# Legoduino.net
KiCad netlist of a schematic drawn in EAGLE
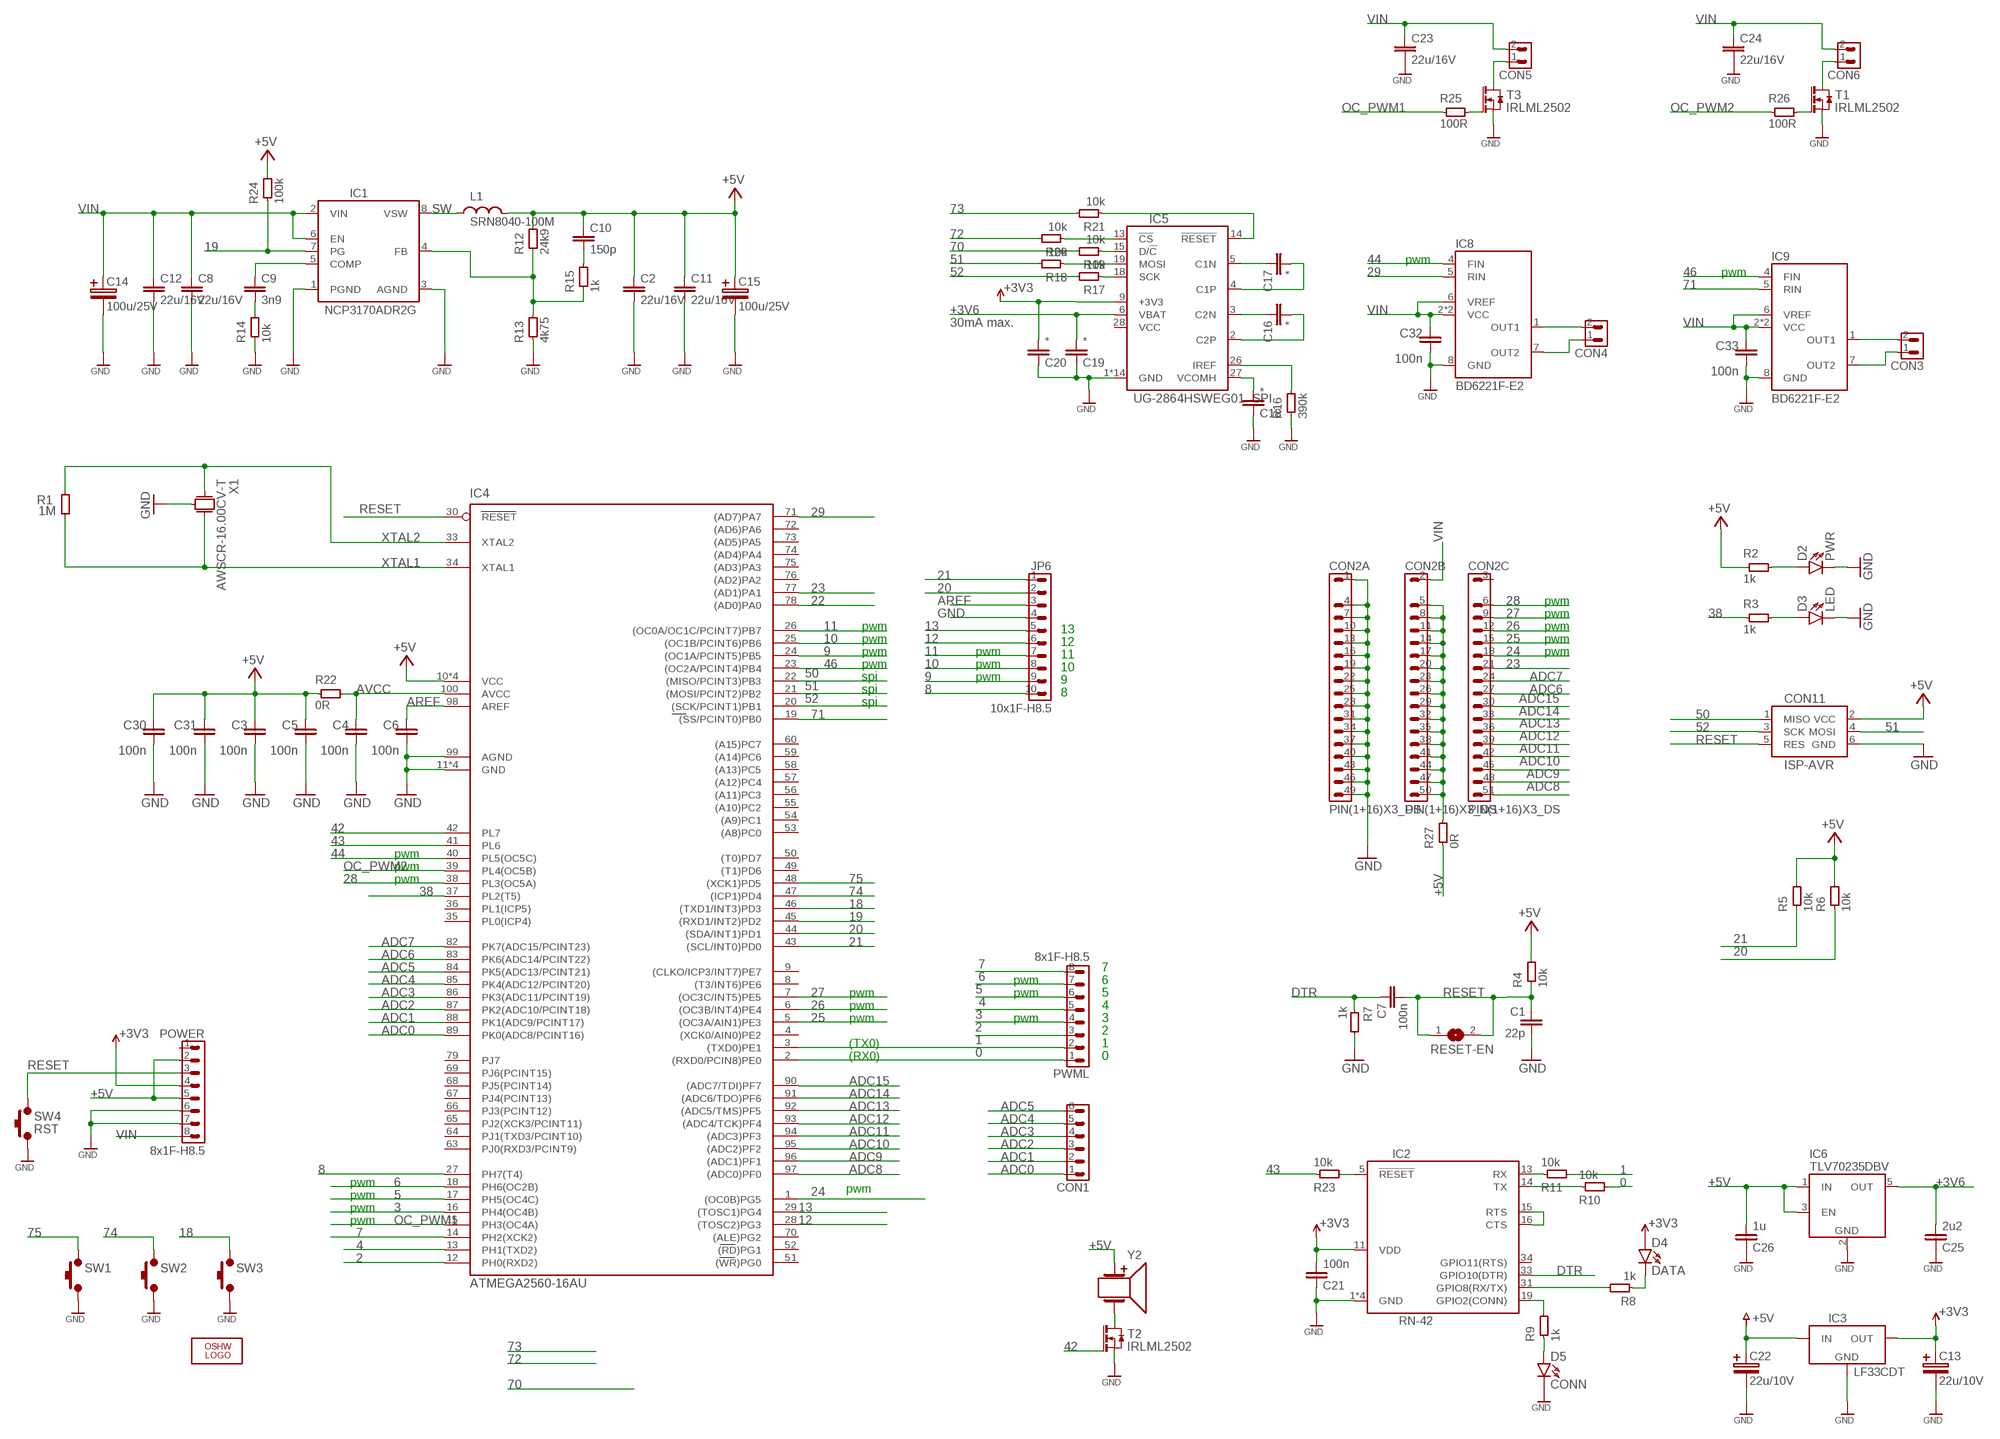
[diagram p0: schematic, sheet 1]

(export (version "E")
  (design (tool "Eeschema 10.0.6"))
  (components
    (comp (ref "C1")
      (value "22p")
      (footprint "eagle-import:0603")
      (libsource (lib "eagle-import") (part "C0603"))
    )
    (comp (ref "C2")
      (value "22u/16V")
      (footprint "eagle-import:1210")
      (libsource (lib "eagle-import") (part "C1210"))
    )
    (comp (ref "C3")
      (value "100n")
      (footprint "eagle-import:0603")
      (libsource (lib "eagle-import") (part "C0603"))
    )
    (comp (ref "C4")
      (value "100n")
      (footprint "eagle-import:0603")
      (libsource (lib "eagle-import") (part "C0603"))
    )
    (comp (ref "C5")
      (value "100n")
      (footprint "eagle-import:0603")
      (libsource (lib "eagle-import") (part "C0603"))
    )
    (comp (ref "C6")
      (value "100n")
      (footprint "eagle-import:0603")
      (libsource (lib "eagle-import") (part "C0603"))
    )
    (comp (ref "C7")
      (value "100n")
      (footprint "eagle-import:0603")
      (libsource (lib "eagle-import") (part "C0603"))
    )
    (comp (ref "C8")
      (value "22u/16V")
      (footprint "eagle-import:1210")
      (libsource (lib "eagle-import") (part "C1210"))
    )
    (comp (ref "C9")
      (value "3n9")
      (footprint "eagle-import:0603")
      (libsource (lib "eagle-import") (part "C0603"))
    )
    (comp (ref "C10")
      (value "150p")
      (footprint "eagle-import:0603")
      (libsource (lib "eagle-import") (part "C0603"))
    )
    (comp (ref "C11")
      (value "22u/16V")
      (footprint "eagle-import:1210")
      (libsource (lib "eagle-import") (part "C1210"))
    )
    (comp (ref "C12")
      (value "22u/16V")
      (footprint "eagle-import:1210")
      (libsource (lib "eagle-import") (part "C1210"))
    )
    (comp (ref "C13")
      (value "22u/10V")
      (footprint "eagle-import:SMC_A")
      (libsource (lib "eagle-import") (part "Pietrucha_CE-SMC_A"))
    )
    (comp (ref "C14")
      (value "100u/25V")
      (footprint "eagle-import:CE_SMD6.3")
      (libsource (lib "eagle-import") (part "CE_SMD6.3"))
    )
    (comp (ref "C15")
      (value "100u/25V")
      (footprint "eagle-import:CE_SMD6.3")
      (libsource (lib "eagle-import") (part "CE_SMD6.3"))
    )
    (comp (ref "C16")
      (value "*")
      (footprint "eagle-import:0603")
      (libsource (lib "eagle-import") (part "C0603"))
    )
    (comp (ref "C17")
      (value "*")
      (footprint "eagle-import:0603")
      (libsource (lib "eagle-import") (part "C0603"))
    )
    (comp (ref "C18")
      (value "*")
      (footprint "eagle-import:0603")
      (libsource (lib "eagle-import") (part "C0603"))
    )
    (comp (ref "C19")
      (value "*")
      (footprint "eagle-import:0603")
      (libsource (lib "eagle-import") (part "C0603"))
    )
    (comp (ref "C20")
      (value "*")
      (footprint "eagle-import:0603")
      (libsource (lib "eagle-import") (part "C0603"))
    )
    (comp (ref "C21")
      (value "100n")
      (footprint "eagle-import:0603")
      (libsource (lib "eagle-import") (part "C0603"))
    )
    (comp (ref "C22")
      (value "22u/10V")
      (footprint "eagle-import:SMC_A")
      (libsource (lib "eagle-import") (part "Pietrucha_CE-SMC_A"))
    )
    (comp (ref "C23")
      (value "22u/16V")
      (footprint "eagle-import:1210")
      (libsource (lib "eagle-import") (part "C1210"))
    )
    (comp (ref "C24")
      (value "22u/16V")
      (footprint "eagle-import:1210")
      (libsource (lib "eagle-import") (part "C1210"))
    )
    (comp (ref "C25")
      (value "2u2")
      (footprint "eagle-import:0603")
      (libsource (lib "eagle-import") (part "C0603"))
    )
    (comp (ref "C26")
      (value "1u")
      (footprint "eagle-import:0603")
      (libsource (lib "eagle-import") (part "C0603"))
    )
    (comp (ref "C30")
      (value "100n")
      (footprint "eagle-import:0603")
      (libsource (lib "eagle-import") (part "C0603"))
    )
    (comp (ref "C31")
      (value "100n")
      (footprint "eagle-import:0603")
      (libsource (lib "eagle-import") (part "C0603"))
    )
    (comp (ref "C32")
      (value "100n")
      (footprint "eagle-import:0603")
      (libsource (lib "eagle-import") (part "C0603"))
    )
    (comp (ref "C33")
      (value "100n")
      (footprint "eagle-import:0603")
      (libsource (lib "eagle-import") (part "C0603"))
    )
    (comp (ref "CON1")
      (value "PIN6X1C")
      (footprint "eagle-import:PIN6X1C")
      (libsource (lib "eagle-import") (part "PIN6X1C"))
    )
    (comp (ref "CON2")
      (value "PIN(1+16)X3_DS")
      (footprint "eagle-import:PIN(1+16)X3_DS")
      (libsource (lib "eagle-import") (part "PIN(1+16)X3_DS"))
    )
    (comp (ref "CON3")
      (value "PIN2X1C")
      (footprint "eagle-import:PIN2X1C")
      (libsource (lib "eagle-import") (part "PIN2X1C"))
    )
    (comp (ref "CON4")
      (value "PIN2X1C")
      (footprint "eagle-import:PIN2X1C")
      (libsource (lib "eagle-import") (part "PIN2X1C"))
    )
    (comp (ref "CON5")
      (value "PIN2X1C")
      (footprint "eagle-import:PIN2X1C")
      (libsource (lib "eagle-import") (part "PIN2X1C"))
    )
    (comp (ref "CON6")
      (value "PIN2X1C")
      (footprint "eagle-import:PIN2X1C")
      (libsource (lib "eagle-import") (part "PIN2X1C"))
    )
    (comp (ref "CON11")
      (value "ISP-AVR")
      (footprint "eagle-import:PIN3X2")
      (libsource (lib "eagle-import") (part "ISP-AVR"))
    )
    (comp (ref "D2")
      (value "PWR")
      (footprint "eagle-import:D0805")
      (libsource (lib "eagle-import") (part "LED0805"))
    )
    (comp (ref "D3")
      (value "LED")
      (footprint "eagle-import:D0805")
      (libsource (lib "eagle-import") (part "LED0805"))
    )
    (comp (ref "D4")
      (value "DATA")
      (footprint "eagle-import:D0805")
      (libsource (lib "eagle-import") (part "LED0805"))
    )
    (comp (ref "D5")
      (value "CONN")
      (footprint "eagle-import:D0805")
      (libsource (lib "eagle-import") (part "LED0805"))
    )
    (comp (ref "IC1")
      (value "NCP3170ADR2G")
      (footprint "eagle-import:SO08")
      (libsource (lib "eagle-import") (part "NCP3170DR2GA"))
    )
    (comp (ref "IC2")
      (value "RN-42")
      (footprint "eagle-import:RN42")
      (libsource (lib "eagle-import") (part "RN-42"))
    )
    (comp (ref "IC3")
      (value "LF33CDT")
      (footprint "eagle-import:DPAK")
      (libsource (lib "eagle-import") (part "LFCDT33"))
    )
    (comp (ref "IC4")
      (value "ATMEGA2560-16AU")
      (footprint "eagle-import:TQFP100")
      (libsource (lib "eagle-import") (part "ATMEGA2560AU-16"))
    )
    (comp (ref "IC5")
      (value "UG-2864HSWEG01_SPI")
      (footprint "eagle-import:UG-2864HSWEG01")
      (libsource (lib "eagle-import") (part "UG-2864HSWEG01_SPI"))
    )
    (comp (ref "IC6")
      (value "TLV70235DBV")
      (footprint "eagle-import:SOT23-5")
      (libsource (lib "eagle-import") (part "TLV702DBV35"))
    )
    (comp (ref "IC8")
      (value "BD6221F-E2")
      (footprint "eagle-import:SO08")
      (libsource (lib "eagle-import") (part "BD6221F-E2"))
    )
    (comp (ref "IC9")
      (value "BD6221F-E2")
      (footprint "eagle-import:SO08")
      (libsource (lib "eagle-import") (part "BD6221F-E2"))
    )
    (comp (ref "JP6")
      (value "10x1F-H8.5")
      (footprint "eagle-import:PIN10X1C")
      (libsource (lib "eagle-import") (part "PIN10X1C"))
    )
    (comp (ref "L1")
      (value "SRN8040-100M")
      (footprint "eagle-import:SRN8040")
      (libsource (lib "eagle-import") (part "SRN8040-100M"))
    )
    (comp (ref "LOGO1")
      (value "OSHW_LOGO_10MILX0200-NT")
      (footprint "eagle-import:OSHW_10X200_NOTEXT")
      (libsource (lib "eagle-import") (part "OSHW_LOGO_10MILX0200-NT"))
    )
    (comp (ref "POWER")
      (value "8x1F-H8.5")
      (footprint "eagle-import:PIN8X1C")
      (libsource (lib "eagle-import") (part "PIN8X1C"))
    )
    (comp (ref "PWML")
      (value "8x1F-H8.5")
      (footprint "eagle-import:PIN8X1C")
      (libsource (lib "eagle-import") (part "PIN8X1C"))
    )
    (comp (ref "R1")
      (value "1M")
      (footprint "eagle-import:0603")
      (libsource (lib "eagle-import") (part "R0603"))
    )
    (comp (ref "R2")
      (value "1k")
      (footprint "eagle-import:0603")
      (libsource (lib "eagle-import") (part "R0603"))
    )
    (comp (ref "R3")
      (value "1k")
      (footprint "eagle-import:0603")
      (libsource (lib "eagle-import") (part "R0603"))
    )
    (comp (ref "R4")
      (value "10k")
      (footprint "eagle-import:0603")
      (libsource (lib "eagle-import") (part "R0603"))
    )
    (comp (ref "R5")
      (value "10k")
      (footprint "eagle-import:0603")
      (libsource (lib "eagle-import") (part "R0603"))
    )
    (comp (ref "R6")
      (value "10k")
      (footprint "eagle-import:0603")
      (libsource (lib "eagle-import") (part "R0603"))
    )
    (comp (ref "R7")
      (value "1k")
      (footprint "eagle-import:0603")
      (libsource (lib "eagle-import") (part "R0603"))
    )
    (comp (ref "R8")
      (value "1k")
      (footprint "eagle-import:0603")
      (libsource (lib "eagle-import") (part "R0603"))
    )
    (comp (ref "R9")
      (value "1k")
      (footprint "eagle-import:0603")
      (libsource (lib "eagle-import") (part "R0603"))
    )
    (comp (ref "R10")
      (value "10k")
      (footprint "eagle-import:0603")
      (libsource (lib "eagle-import") (part "R0603"))
    )
    (comp (ref "R11")
      (value "10k")
      (footprint "eagle-import:0603")
      (libsource (lib "eagle-import") (part "R0603"))
    )
    (comp (ref "R12")
      (value "24k9")
      (footprint "eagle-import:0603")
      (libsource (lib "eagle-import") (part "R0603"))
    )
    (comp (ref "R13")
      (value "4k75")
      (footprint "eagle-import:0603")
      (libsource (lib "eagle-import") (part "R0603"))
    )
    (comp (ref "R14")
      (value "10k")
      (footprint "eagle-import:0603")
      (libsource (lib "eagle-import") (part "R0603"))
    )
    (comp (ref "R15")
      (value "1k")
      (footprint "eagle-import:0603")
      (libsource (lib "eagle-import") (part "R0603"))
    )
    (comp (ref "R16")
      (value "390k")
      (footprint "eagle-import:0603")
      (libsource (lib "eagle-import") (part "R0603"))
    )
    (comp (ref "R17")
      (value "10k")
      (footprint "eagle-import:0603")
      (libsource (lib "eagle-import") (part "R0603"))
    )
    (comp (ref "R18")
      (value "10k")
      (footprint "eagle-import:0603")
      (libsource (lib "eagle-import") (part "R0603"))
    )
    (comp (ref "R19")
      (value "10k")
      (footprint "eagle-import:0603")
      (libsource (lib "eagle-import") (part "R0603"))
    )
    (comp (ref "R20")
      (value "10k")
      (footprint "eagle-import:0603")
      (libsource (lib "eagle-import") (part "R0603"))
    )
    (comp (ref "R21")
      (value "10k")
      (footprint "eagle-import:0603")
      (libsource (lib "eagle-import") (part "R0603"))
    )
    (comp (ref "R22")
      (value "0R")
      (footprint "eagle-import:0603")
      (libsource (lib "eagle-import") (part "R0603"))
    )
    (comp (ref "R23")
      (value "10k")
      (footprint "eagle-import:0603")
      (libsource (lib "eagle-import") (part "R0603"))
    )
    (comp (ref "R24")
      (value "100k")
      (footprint "eagle-import:0603")
      (libsource (lib "eagle-import") (part "R0603"))
    )
    (comp (ref "R25")
      (value "100R")
      (footprint "eagle-import:0603")
      (libsource (lib "eagle-import") (part "R0603"))
    )
    (comp (ref "R26")
      (value "100R")
      (footprint "eagle-import:0603")
      (libsource (lib "eagle-import") (part "R0603"))
    )
    (comp (ref "R27")
      (value "0R")
      (footprint "eagle-import:0805")
      (libsource (lib "eagle-import") (part "R0805"))
    )
    (comp (ref "RESET-EN")
      (value "SJ")
      (footprint "eagle-import:SJ")
      (libsource (lib "eagle-import") (part "SJ"))
    )
    (comp (ref "SW1")
      (value "SW_SMD")
      (footprint "eagle-import:MICROSW_SMD")
      (libsource (lib "eagle-import") (part "SW_SMD"))
    )
    (comp (ref "SW2")
      (value "SW_SMD")
      (footprint "eagle-import:MICROSW_SMD")
      (libsource (lib "eagle-import") (part "SW_SMD"))
    )
    (comp (ref "SW3")
      (value "SW_SMD")
      (footprint "eagle-import:MICROSW_SMD")
      (libsource (lib "eagle-import") (part "SW_SMD"))
    )
    (comp (ref "SW4")
      (value "RST")
      (footprint "eagle-import:MICROSW_SMD")
      (libsource (lib "eagle-import") (part "SW_SMD"))
    )
    (comp (ref "T1")
      (value "IRLML2502")
      (footprint "eagle-import:SOT23")
      (libsource (lib "eagle-import") (part "IRLML2502"))
    )
    (comp (ref "T2")
      (value "IRLML2502")
      (footprint "eagle-import:SOT23")
      (libsource (lib "eagle-import") (part "IRLML2502"))
    )
    (comp (ref "T3")
      (value "IRLML2502")
      (footprint "eagle-import:SOT23")
      (libsource (lib "eagle-import") (part "IRLML2502"))
    )
    (comp (ref "X1")
      (value "AWSCR-16.00CV-T")
      (footprint "eagle-import:CERAMIC_3.7X3.1")
      (libsource (lib "eagle-import") (part "AWSCRCV-T-16.00"))
    )
    (comp (ref "Y2")
      (value "BUZZER-HCM")
      (footprint "eagle-import:BUZZER-HCM")
      (libsource (lib "eagle-import") (part "BUZZER-HCM"))
    )
  )
  (nets
    (net (code "1") (name "+3V3") (class "Default")
      (node (ref "C13") (pin "+") (pinfunction "+_+") (pintype "passive"))
      (node (ref "C20") (pin "2") (pinfunction "2_2") (pintype "passive"))
      (node (ref "C21") (pin "2") (pinfunction "2_2") (pintype "passive"))
      (node (ref "D4") (pin "A") (pinfunction "A_A") (pintype "passive"))
      (node (ref "IC2") (pin "11") (pinfunction "VDD_11") (pintype "power_in"))
      (node (ref "IC3") (pin "3") (pinfunction "OUT_3") (pintype "passive"))
      (node (ref "IC5") (pin "9") (pinfunction "+3V3_9") (pintype "power_in"))
      (node (ref "POWER") (pin "4") (pinfunction "4_4") (pintype "passive"))
    )
    (net (code "2") (name "+5V") (class "Default")
      (node (ref "C10") (pin "1") (pinfunction "1_1") (pintype "passive"))
      (node (ref "C11") (pin "1") (pinfunction "1_1") (pintype "passive"))
      (node (ref "C15") (pin "+") (pinfunction "+_+") (pintype "passive"))
      (node (ref "C2") (pin "1") (pinfunction "1_1") (pintype "passive"))
      (node (ref "C22") (pin "+") (pinfunction "+_+") (pintype "passive"))
      (node (ref "C26") (pin "2") (pinfunction "2_2") (pintype "passive"))
      (node (ref "C3") (pin "1") (pinfunction "1_1") (pintype "passive"))
      (node (ref "C30") (pin "1") (pinfunction "1_1") (pintype "passive"))
      (node (ref "C31") (pin "1") (pinfunction "1_1") (pintype "passive"))
      (node (ref "C5") (pin "1") (pinfunction "1_1") (pintype "passive"))
      (node (ref "CON11") (pin "2") (pinfunction "VCC_2") (pintype "passive"))
      (node (ref "IC3") (pin "1") (pinfunction "IN_1") (pintype "input"))
      (node (ref "IC4") (pin "10") (pinfunction "VCC_10") (pintype "power_in"))
      (node (ref "IC4") (pin "31") (pinfunction "VCC_31") (pintype "power_in"))
      (node (ref "IC4") (pin "61") (pinfunction "VCC_61") (pintype "power_in"))
      (node (ref "IC4") (pin "80") (pinfunction "VCC_80") (pintype "power_in"))
      (node (ref "IC6") (pin "1") (pinfunction "IN_1") (pintype "input"))
      (node (ref "IC6") (pin "3") (pinfunction "EN_3") (pintype "input"))
      (node (ref "L1") (pin "2") (pinfunction "2_2") (pintype "passive"))
      (node (ref "POWER") (pin "2") (pinfunction "2_2") (pintype "passive"))
      (node (ref "POWER") (pin "5") (pinfunction "5_5") (pintype "passive"))
      (node (ref "R12") (pin "2") (pinfunction "2_2") (pintype "passive"))
      (node (ref "R2") (pin "1") (pinfunction "1_1") (pintype "passive"))
      (node (ref "R22") (pin "1") (pinfunction "1_1") (pintype "passive"))
      (node (ref "R24") (pin "2") (pinfunction "2_2") (pintype "passive"))
      (node (ref "R27") (pin "1") (pinfunction "1_1") (pintype "passive"))
      (node (ref "R4") (pin "2") (pinfunction "2_2") (pintype "passive"))
      (node (ref "R5") (pin "2") (pinfunction "2_2") (pintype "passive"))
      (node (ref "R6") (pin "2") (pinfunction "2_2") (pintype "passive"))
      (node (ref "Y2") (pin "+") (pinfunction "+_+") (pintype "passive"))
    )
    (net (code "3") (name "/+3V6") (class "Default")
      (node (ref "C19") (pin "2") (pinfunction "2_2") (pintype "passive"))
      (node (ref "C25") (pin "2") (pinfunction "2_2") (pintype "passive"))
      (node (ref "IC5") (pin "6") (pinfunction "VBAT_6") (pintype "power_in"))
      (node (ref "IC6") (pin "5") (pinfunction "OUT_5") (pintype "passive"))
    )
    (net (code "4") (name "/0") (class "Default")
      (node (ref "IC4") (pin "2") (pinfunction "(RXD0/PCIN8)PE0_2") (pintype "bidirectional"))
      (node (ref "PWML") (pin "1") (pinfunction "1_1") (pintype "passive"))
      (node (ref "R10") (pin "2") (pinfunction "2_2") (pintype "passive"))
    )
    (net (code "5") (name "/1") (class "Default")
      (node (ref "IC4") (pin "3") (pinfunction "(TXD0)PE1_3") (pintype "bidirectional"))
      (node (ref "PWML") (pin "2") (pinfunction "2_2") (pintype "passive"))
      (node (ref "R11") (pin "2") (pinfunction "2_2") (pintype "passive"))
    )
    (net (code "6") (name "/2") (class "Default")
      (node (ref "IC4") (pin "12") (pinfunction "PH0(RXD2)_12") (pintype "bidirectional"))
      (node (ref "PWML") (pin "3") (pinfunction "3_3") (pintype "passive"))
    )
    (net (code "7") (name "/3") (class "Default")
      (node (ref "IC4") (pin "16") (pinfunction "PH4(OC4B)_16") (pintype "bidirectional"))
      (node (ref "PWML") (pin "4") (pinfunction "4_4") (pintype "passive"))
    )
    (net (code "8") (name "/4") (class "Default")
      (node (ref "IC4") (pin "13") (pinfunction "PH1(TXD2)_13") (pintype "bidirectional"))
      (node (ref "PWML") (pin "5") (pinfunction "5_5") (pintype "passive"))
    )
    (net (code "9") (name "/5") (class "Default")
      (node (ref "IC4") (pin "17") (pinfunction "PH5(OC4C)_17") (pintype "bidirectional"))
      (node (ref "PWML") (pin "6") (pinfunction "6_6") (pintype "passive"))
    )
    (net (code "10") (name "/6") (class "Default")
      (node (ref "IC4") (pin "18") (pinfunction "PH6(OC2B)_18") (pintype "bidirectional"))
      (node (ref "PWML") (pin "7") (pinfunction "7_7") (pintype "passive"))
    )
    (net (code "11") (name "/7") (class "Default")
      (node (ref "IC4") (pin "14") (pinfunction "PH2(XCK2)_14") (pintype "bidirectional"))
      (node (ref "PWML") (pin "8") (pinfunction "8_8") (pintype "passive"))
    )
    (net (code "12") (name "/8") (class "Default")
      (node (ref "IC4") (pin "27") (pinfunction "PH7(T4)_27") (pintype "bidirectional"))
      (node (ref "JP6") (pin "10") (pinfunction "10_10") (pintype "passive"))
    )
    (net (code "13") (name "/9") (class "Default")
      (node (ref "IC4") (pin "24") (pinfunction "(OC1A/PCINT5)PB5_24") (pintype "bidirectional"))
      (node (ref "JP6") (pin "9") (pinfunction "9_9") (pintype "passive"))
    )
    (net (code "14") (name "/10") (class "Default")
      (node (ref "IC4") (pin "25") (pinfunction "(OC1B/PCINT6)PB6_25") (pintype "bidirectional"))
      (node (ref "JP6") (pin "8") (pinfunction "8_8") (pintype "passive"))
    )
    (net (code "15") (name "/11") (class "Default")
      (node (ref "IC4") (pin "26") (pinfunction "(OC0A/OC1C/PCINT7)PB7_26") (pintype "bidirectional"))
      (node (ref "JP6") (pin "7") (pinfunction "7_7") (pintype "passive"))
    )
    (net (code "16") (name "/12") (class "Default")
      (node (ref "IC4") (pin "28") (pinfunction "(TOSC2)PG3_28") (pintype "bidirectional"))
      (node (ref "JP6") (pin "6") (pinfunction "6_6") (pintype "passive"))
    )
    (net (code "17") (name "/13") (class "Default")
      (node (ref "IC4") (pin "29") (pinfunction "(TOSC1)PG4_29") (pintype "bidirectional"))
      (node (ref "JP6") (pin "5") (pinfunction "5_5") (pintype "passive"))
    )
    (net (code "18") (name "/18") (class "Default")
      (node (ref "IC4") (pin "46") (pinfunction "(TXD1/INT3)PD3_46") (pintype "bidirectional"))
      (node (ref "SW3") (pin "1") (pinfunction "1_1") (pintype "passive"))
      (node (ref "SW3") (pin "1A") (pinfunction "1_1A") (pintype "passive"))
    )
    (net (code "19") (name "/19") (class "Default")
      (node (ref "IC1") (pin "7") (pinfunction "PG_7") (pintype "open_collector"))
      (node (ref "IC4") (pin "45") (pinfunction "(RXD1/INT2)PD2_45") (pintype "bidirectional"))
      (node (ref "R24") (pin "1") (pinfunction "1_1") (pintype "passive"))
    )
    (net (code "20") (name "/20") (class "Default")
      (node (ref "IC4") (pin "44") (pinfunction "(SDA/INT1)PD1_44") (pintype "bidirectional"))
      (node (ref "JP6") (pin "2") (pinfunction "2_2") (pintype "passive"))
      (node (ref "R6") (pin "1") (pinfunction "1_1") (pintype "passive"))
    )
    (net (code "21") (name "/21") (class "Default")
      (node (ref "IC4") (pin "43") (pinfunction "(SCL/INT0)PD0_43") (pintype "bidirectional"))
      (node (ref "JP6") (pin "1") (pinfunction "1_1") (pintype "passive"))
      (node (ref "R5") (pin "1") (pinfunction "1_1") (pintype "passive"))
    )
    (net (code "22") (name "/22") (class "Default")
      (node (ref "IC4") (pin "78") (pinfunction "(AD0)PA0_78") (pintype "bidirectional"))
    )
    (net (code "23") (name "/23") (class "Default")
      (node (ref "CON2") (pin "21") (pinfunction "7_21") (pintype "passive"))
      (node (ref "IC4") (pin "77") (pinfunction "(AD1)PA1_77") (pintype "bidirectional"))
    )
    (net (code "24") (name "/24") (class "Default")
      (node (ref "CON2") (pin "18") (pinfunction "6_18") (pintype "passive"))
      (node (ref "IC4") (pin "1") (pinfunction "(OC0B)PG5_1") (pintype "bidirectional"))
    )
    (net (code "25") (name "/25") (class "Default")
      (node (ref "CON2") (pin "15") (pinfunction "5_15") (pintype "passive"))
      (node (ref "IC4") (pin "5") (pinfunction "(OC3A/AIN1)PE3_5") (pintype "bidirectional"))
    )
    (net (code "26") (name "/26") (class "Default")
      (node (ref "CON2") (pin "12") (pinfunction "4_12") (pintype "passive"))
      (node (ref "IC4") (pin "6") (pinfunction "(OC3B/INT4)PE4_6") (pintype "bidirectional"))
    )
    (net (code "27") (name "/27") (class "Default")
      (node (ref "CON2") (pin "9") (pinfunction "3_9") (pintype "passive"))
      (node (ref "IC4") (pin "7") (pinfunction "(OC3C/INT5)PE5_7") (pintype "bidirectional"))
    )
    (net (code "28") (name "/28") (class "Default")
      (node (ref "CON2") (pin "6") (pinfunction "2_6") (pintype "passive"))
      (node (ref "IC4") (pin "38") (pinfunction "PL3(OC5A)_38") (pintype "bidirectional"))
    )
    (net (code "29") (name "/29") (class "Default")
      (node (ref "IC4") (pin "71") (pinfunction "(AD7)PA7_71") (pintype "bidirectional"))
      (node (ref "IC8") (pin "5") (pinfunction "RIN_5") (pintype "input"))
    )
    (net (code "30") (name "/38") (class "Default")
      (node (ref "IC4") (pin "37") (pinfunction "PL2(T5)_37") (pintype "bidirectional"))
      (node (ref "R3") (pin "1") (pinfunction "1_1") (pintype "passive"))
    )
    (net (code "31") (name "/42") (class "Default")
      (node (ref "IC4") (pin "42") (pinfunction "PL7_42") (pintype "bidirectional"))
      (node (ref "T2") (pin "1") (pinfunction "G_1") (pintype "passive"))
    )
    (net (code "32") (name "/43") (class "Default")
      (node (ref "IC4") (pin "41") (pinfunction "PL6_41") (pintype "bidirectional"))
      (node (ref "R23") (pin "1") (pinfunction "1_1") (pintype "passive"))
    )
    (net (code "33") (name "/44") (class "Default")
      (node (ref "IC4") (pin "40") (pinfunction "PL5(OC5C)_40") (pintype "bidirectional"))
      (node (ref "IC8") (pin "4") (pinfunction "FIN_4") (pintype "input"))
    )
    (net (code "34") (name "/46") (class "Default")
      (node (ref "IC4") (pin "23") (pinfunction "(OC2A/PCINT4)PB4_23") (pintype "bidirectional"))
      (node (ref "IC9") (pin "4") (pinfunction "FIN_4") (pintype "input"))
    )
    (net (code "35") (name "/50") (class "Default")
      (node (ref "CON11") (pin "1") (pinfunction "MISO_1") (pintype "passive"))
      (node (ref "IC4") (pin "22") (pinfunction "(MISO/PCINT3)PB3_22") (pintype "bidirectional"))
    )
    (net (code "36") (name "/51") (class "Default")
      (node (ref "CON11") (pin "4") (pinfunction "MOSI_4") (pintype "passive"))
      (node (ref "IC4") (pin "21") (pinfunction "(MOSI/PCINT2)PB2_21") (pintype "bidirectional"))
      (node (ref "R18") (pin "2") (pinfunction "2_2") (pintype "passive"))
    )
    (net (code "37") (name "/52") (class "Default")
      (node (ref "CON11") (pin "3") (pinfunction "SCK_3") (pintype "passive"))
      (node (ref "IC4") (pin "20") (pinfunction "(SCK/PCINT1)PB1_20") (pintype "bidirectional"))
      (node (ref "R17") (pin "2") (pinfunction "2_2") (pintype "passive"))
    )
    (net (code "38") (name "/70") (class "Default")
      (node (ref "R19") (pin "2") (pinfunction "2_2") (pintype "passive"))
    )
    (net (code "39") (name "/71") (class "Default")
      (node (ref "IC4") (pin "19") (pinfunction "(SS/PCINT0)PB0_19") (pintype "bidirectional"))
      (node (ref "IC9") (pin "5") (pinfunction "RIN_5") (pintype "input"))
    )
    (net (code "40") (name "/72") (class "Default")
      (node (ref "R20") (pin "2") (pinfunction "2_2") (pintype "passive"))
    )
    (net (code "41") (name "/73") (class "Default")
      (node (ref "R21") (pin "2") (pinfunction "2_2") (pintype "passive"))
    )
    (net (code "42") (name "/74") (class "Default")
      (node (ref "IC4") (pin "47") (pinfunction "(ICP1)PD4_47") (pintype "bidirectional"))
      (node (ref "SW2") (pin "1") (pinfunction "1_1") (pintype "passive"))
      (node (ref "SW2") (pin "1A") (pinfunction "1_1A") (pintype "passive"))
    )
    (net (code "43") (name "/75") (class "Default")
      (node (ref "IC4") (pin "48") (pinfunction "(XCK1)PD5_48") (pintype "bidirectional"))
      (node (ref "SW1") (pin "1") (pinfunction "1_1") (pintype "passive"))
      (node (ref "SW1") (pin "1A") (pinfunction "1_1A") (pintype "passive"))
    )
    (net (code "44") (name "/ADC0") (class "Default")
      (node (ref "CON1") (pin "1") (pinfunction "1_1") (pintype "passive"))
      (node (ref "IC4") (pin "89") (pinfunction "PK0(ADC8/PCINT16)_89") (pintype "bidirectional"))
    )
    (net (code "45") (name "/ADC1") (class "Default")
      (node (ref "CON1") (pin "2") (pinfunction "2_2") (pintype "passive"))
      (node (ref "IC4") (pin "88") (pinfunction "PK1(ADC9/PCINT17)_88") (pintype "bidirectional"))
    )
    (net (code "46") (name "/ADC2") (class "Default")
      (node (ref "CON1") (pin "3") (pinfunction "3_3") (pintype "passive"))
      (node (ref "IC4") (pin "87") (pinfunction "PK2(ADC10/PCINT18)_87") (pintype "bidirectional"))
    )
    (net (code "47") (name "/ADC3") (class "Default")
      (node (ref "CON1") (pin "4") (pinfunction "4_4") (pintype "passive"))
      (node (ref "IC4") (pin "86") (pinfunction "PK3(ADC11/PCINT19)_86") (pintype "bidirectional"))
    )
    (net (code "48") (name "/ADC4") (class "Default")
      (node (ref "CON1") (pin "5") (pinfunction "5_5") (pintype "passive"))
      (node (ref "IC4") (pin "85") (pinfunction "PK4(ADC12/PCINT20)_85") (pintype "bidirectional"))
    )
    (net (code "49") (name "/ADC5") (class "Default")
      (node (ref "CON1") (pin "6") (pinfunction "6_6") (pintype "passive"))
      (node (ref "IC4") (pin "84") (pinfunction "PK5(ADC13/PCINT21)_84") (pintype "bidirectional"))
    )
    (net (code "50") (name "/ADC6") (class "Default")
      (node (ref "CON2") (pin "27") (pinfunction "9_27") (pintype "passive"))
      (node (ref "IC4") (pin "83") (pinfunction "PK6(ADC14/PCINT22)_83") (pintype "bidirectional"))
    )
    (net (code "51") (name "/ADC7") (class "Default")
      (node (ref "CON2") (pin "24") (pinfunction "8_24") (pintype "passive"))
      (node (ref "IC4") (pin "82") (pinfunction "PK7(ADC15/PCINT23)_82") (pintype "bidirectional"))
    )
    (net (code "52") (name "/ADC8") (class "Default")
      (node (ref "CON2") (pin "51") (pinfunction "17_51") (pintype "passive"))
      (node (ref "IC4") (pin "97") (pinfunction "(ADC0)PF0_97") (pintype "bidirectional"))
    )
    (net (code "53") (name "/ADC9") (class "Default")
      (node (ref "CON2") (pin "48") (pinfunction "16_48") (pintype "passive"))
      (node (ref "IC4") (pin "96") (pinfunction "(ADC1)PF1_96") (pintype "bidirectional"))
    )
    (net (code "54") (name "/ADC10") (class "Default")
      (node (ref "CON2") (pin "45") (pinfunction "15_45") (pintype "passive"))
      (node (ref "IC4") (pin "95") (pinfunction "(ADC2)PF2_95") (pintype "bidirectional"))
    )
    (net (code "55") (name "/ADC11") (class "Default")
      (node (ref "CON2") (pin "42") (pinfunction "14_42") (pintype "passive"))
      (node (ref "IC4") (pin "94") (pinfunction "(ADC3)PF3_94") (pintype "bidirectional"))
    )
    (net (code "56") (name "/ADC12") (class "Default")
      (node (ref "CON2") (pin "39") (pinfunction "13_39") (pintype "passive"))
      (node (ref "IC4") (pin "93") (pinfunction "(ADC4/TCK)PF4_93") (pintype "bidirectional"))
    )
    (net (code "57") (name "/ADC13") (class "Default")
      (node (ref "CON2") (pin "36") (pinfunction "12_36") (pintype "passive"))
      (node (ref "IC4") (pin "92") (pinfunction "(ADC5/TMS)PF5_92") (pintype "bidirectional"))
    )
    (net (code "58") (name "/ADC14") (class "Default")
      (node (ref "CON2") (pin "33") (pinfunction "11_33") (pintype "passive"))
      (node (ref "IC4") (pin "91") (pinfunction "(ADC6/TDO)PF6_91") (pintype "bidirectional"))
    )
    (net (code "59") (name "/ADC15") (class "Default")
      (node (ref "CON2") (pin "30") (pinfunction "10_30") (pintype "passive"))
      (node (ref "IC4") (pin "90") (pinfunction "(ADC7/TDI)PF7_90") (pintype "bidirectional"))
    )
    (net (code "60") (name "/AREF") (class "Default")
      (node (ref "C6") (pin "1") (pinfunction "1_1") (pintype "passive"))
      (node (ref "IC4") (pin "98") (pinfunction "AREF_98") (pintype "bidirectional"))
      (node (ref "JP6") (pin "3") (pinfunction "3_3") (pintype "passive"))
    )
    (net (code "61") (name "/AVCC") (class "Default")
      (node (ref "C4") (pin "1") (pinfunction "1_1") (pintype "passive"))
      (node (ref "IC4") (pin "100") (pinfunction "AVCC_100") (pintype "power_in"))
      (node (ref "R22") (pin "2") (pinfunction "2_2") (pintype "passive"))
    )
    (net (code "62") (name "/DTR") (class "Default")
      (node (ref "C7") (pin "1") (pinfunction "1_1") (pintype "passive"))
      (node (ref "IC2") (pin "33") (pinfunction "GPIO10(DTR)_33") (pintype "bidirectional"))
      (node (ref "R7") (pin "1") (pinfunction "1_1") (pintype "passive"))
    )
    (net (code "63") (name "/OC_PWM1") (class "Default")
      (node (ref "IC4") (pin "15") (pinfunction "PH3(OC4A)_15") (pintype "bidirectional"))
      (node (ref "R25") (pin "1") (pinfunction "1_1") (pintype "passive"))
    )
    (net (code "64") (name "/OC_PWM2") (class "Default")
      (node (ref "IC4") (pin "39") (pinfunction "PL4(OC5B)_39") (pintype "bidirectional"))
      (node (ref "R26") (pin "1") (pinfunction "1_1") (pintype "passive"))
    )
    (net (code "65") (name "/RESET") (class "Default")
      (node (ref "C1") (pin "1") (pinfunction "1_1") (pintype "passive"))
      (node (ref "C7") (pin "2") (pinfunction "2_2") (pintype "passive"))
      (node (ref "CON11") (pin "5") (pinfunction "RES_5") (pintype "passive"))
      (node (ref "IC4") (pin "30") (pinfunction "RESET_30") (pintype "input"))
      (node (ref "POWER") (pin "3") (pinfunction "3_3") (pintype "passive"))
      (node (ref "R4") (pin "1") (pinfunction "1_1") (pintype "passive"))
      (node (ref "RESET-EN") (pin "1") (pinfunction "1_1") (pintype "passive"))
      (node (ref "RESET-EN") (pin "2") (pinfunction "2_2") (pintype "passive"))
      (node (ref "SW4") (pin "1") (pinfunction "1_1") (pintype "passive"))
      (node (ref "SW4") (pin "1A") (pinfunction "1_1A") (pintype "passive"))
    )
    (net (code "66") (name "/SW") (class "Default")
      (node (ref "IC1") (pin "8") (pinfunction "VSW_8") (pintype "output"))
      (node (ref "L1") (pin "1") (pinfunction "1_1") (pintype "passive"))
    )
    (net (code "67") (name "/VCC") (class "Default")
      (node (ref "IC5") (pin "28") (pinfunction "VCC_28") (pintype "power_in"))
    )
    (net (code "68") (name "/VIN") (class "Default")
      (node (ref "C12") (pin "1") (pinfunction "1_1") (pintype "passive"))
      (node (ref "C14") (pin "+") (pinfunction "+_+") (pintype "passive"))
      (node (ref "C23") (pin "1") (pinfunction "1_1") (pintype "passive"))
      (node (ref "C24") (pin "1") (pinfunction "1_1") (pintype "passive"))
      (node (ref "C32") (pin "1") (pinfunction "1_1") (pintype "passive"))
      (node (ref "C33") (pin "1") (pinfunction "1_1") (pintype "passive"))
      (node (ref "C8") (pin "1") (pinfunction "1_1") (pintype "passive"))
      (node (ref "CON2") (pin "2") (pinfunction "1_2") (pintype "passive"))
      (node (ref "CON5") (pin "2") (pinfunction "2_2") (pintype "passive"))
      (node (ref "CON6") (pin "2") (pinfunction "2_2") (pintype "passive"))
      (node (ref "IC1") (pin "2") (pinfunction "VIN_2") (pintype "power_in"))
      (node (ref "IC1") (pin "6") (pinfunction "EN_6") (pintype "input"))
      (node (ref "IC8") (pin "2") (pinfunction "VCC_2") (pintype "power_in"))
      (node (ref "IC8") (pin "3") (pinfunction "VCC_3") (pintype "power_in"))
      (node (ref "IC8") (pin "6") (pinfunction "VREF_6") (pintype "input"))
      (node (ref "IC9") (pin "2") (pinfunction "VCC_2") (pintype "power_in"))
      (node (ref "IC9") (pin "3") (pinfunction "VCC_3") (pintype "power_in"))
      (node (ref "IC9") (pin "6") (pinfunction "VREF_6") (pintype "input"))
      (node (ref "POWER") (pin "8") (pinfunction "8_8") (pintype "passive"))
    )
    (net (code "69") (name "/XTAL1") (class "Default")
      (node (ref "IC4") (pin "34") (pinfunction "XTAL1_34") (pintype "input"))
      (node (ref "R1") (pin "1") (pinfunction "1_1") (pintype "passive"))
      (node (ref "X1") (pin "2") (pinfunction "2_2") (pintype "passive"))
    )
    (net (code "70") (name "/XTAL2") (class "Default")
      (node (ref "IC4") (pin "33") (pinfunction "XTAL2_33") (pintype "output"))
      (node (ref "R1") (pin "2") (pinfunction "2_2") (pintype "passive"))
      (node (ref "X1") (pin "1") (pinfunction "1_1") (pintype "passive"))
    )
    (net (code "71") (name "GND") (class "Default")
      (node (ref "C1") (pin "2") (pinfunction "2_2") (pintype "passive"))
      (node (ref "C11") (pin "2") (pinfunction "2_2") (pintype "passive"))
      (node (ref "C12") (pin "2") (pinfunction "2_2") (pintype "passive"))
      (node (ref "C13") (pin "-") (pinfunction "-_-") (pintype "passive"))
      (node (ref "C14") (pin "-") (pinfunction "-_-") (pintype "passive"))
      (node (ref "C15") (pin "-") (pinfunction "-_-") (pintype "passive"))
      (node (ref "C18") (pin "1") (pinfunction "1_1") (pintype "passive"))
      (node (ref "C19") (pin "1") (pinfunction "1_1") (pintype "passive"))
      (node (ref "C2") (pin "2") (pinfunction "2_2") (pintype "passive"))
      (node (ref "C20") (pin "1") (pinfunction "1_1") (pintype "passive"))
      (node (ref "C21") (pin "1") (pinfunction "1_1") (pintype "passive"))
      (node (ref "C22") (pin "-") (pinfunction "-_-") (pintype "passive"))
      (node (ref "C23") (pin "2") (pinfunction "2_2") (pintype "passive"))
      (node (ref "C24") (pin "2") (pinfunction "2_2") (pintype "passive"))
      (node (ref "C25") (pin "1") (pinfunction "1_1") (pintype "passive"))
      (node (ref "C26") (pin "1") (pinfunction "1_1") (pintype "passive"))
      (node (ref "C3") (pin "2") (pinfunction "2_2") (pintype "passive"))
      (node (ref "C30") (pin "2") (pinfunction "2_2") (pintype "passive"))
      (node (ref "C31") (pin "2") (pinfunction "2_2") (pintype "passive"))
      (node (ref "C32") (pin "2") (pinfunction "2_2") (pintype "passive"))
      (node (ref "C33") (pin "2") (pinfunction "2_2") (pintype "passive"))
      (node (ref "C4") (pin "2") (pinfunction "2_2") (pintype "passive"))
      (node (ref "C5") (pin "2") (pinfunction "2_2") (pintype "passive"))
      (node (ref "C6") (pin "2") (pinfunction "2_2") (pintype "passive"))
      (node (ref "C8") (pin "2") (pinfunction "2_2") (pintype "passive"))
      (node (ref "CON11") (pin "6") (pinfunction "GND_6") (pintype "passive"))
      (node (ref "CON2") (pin "1") (pinfunction "1_1") (pintype "passive"))
      (node (ref "CON2") (pin "10") (pinfunction "4_10") (pintype "passive"))
      (node (ref "CON2") (pin "13") (pinfunction "5_13") (pintype "passive"))
      (node (ref "CON2") (pin "16") (pinfunction "6_16") (pintype "passive"))
      (node (ref "CON2") (pin "19") (pinfunction "7_19") (pintype "passive"))
      (node (ref "CON2") (pin "22") (pinfunction "8_22") (pintype "passive"))
      (node (ref "CON2") (pin "25") (pinfunction "9_25") (pintype "passive"))
      (node (ref "CON2") (pin "28") (pinfunction "10_28") (pintype "passive"))
      (node (ref "CON2") (pin "31") (pinfunction "11_31") (pintype "passive"))
      (node (ref "CON2") (pin "34") (pinfunction "12_34") (pintype "passive"))
      (node (ref "CON2") (pin "37") (pinfunction "13_37") (pintype "passive"))
      (node (ref "CON2") (pin "4") (pinfunction "2_4") (pintype "passive"))
      (node (ref "CON2") (pin "40") (pinfunction "14_40") (pintype "passive"))
      (node (ref "CON2") (pin "43") (pinfunction "15_43") (pintype "passive"))
      (node (ref "CON2") (pin "46") (pinfunction "16_46") (pintype "passive"))
      (node (ref "CON2") (pin "49") (pinfunction "17_49") (pintype "passive"))
      (node (ref "CON2") (pin "7") (pinfunction "3_7") (pintype "passive"))
      (node (ref "D2") (pin "K") (pinfunction "K_K") (pintype "passive"))
      (node (ref "D3") (pin "K") (pinfunction "K_K") (pintype "passive"))
      (node (ref "D5") (pin "K") (pinfunction "K_K") (pintype "passive"))
      (node (ref "IC1") (pin "1") (pinfunction "PGND_1") (pintype "power_in"))
      (node (ref "IC1") (pin "3") (pinfunction "AGND_3") (pintype "power_in"))
      (node (ref "IC2") (pin "1") (pinfunction "GND_1") (pintype "power_in"))
      (node (ref "IC2") (pin "12") (pinfunction "GND_12") (pintype "power_in"))
      (node (ref "IC2") (pin "28") (pinfunction "GND_28") (pintype "power_in"))
      (node (ref "IC2") (pin "29") (pinfunction "GND_29") (pintype "power_in"))
      (node (ref "IC3") (pin "2") (pinfunction "GND_2") (pintype "passive"))
      (node (ref "IC4") (pin "11") (pinfunction "GND_11") (pintype "power_in"))
      (node (ref "IC4") (pin "32") (pinfunction "GND_32") (pintype "power_in"))
      (node (ref "IC4") (pin "62") (pinfunction "GND_62") (pintype "power_in"))
      (node (ref "IC4") (pin "81") (pinfunction "GND_81") (pintype "power_in"))
      (node (ref "IC4") (pin "99") (pinfunction "AGND_99") (pintype "power_in"))
      (node (ref "IC5") (pin "1") (pinfunction "GND_1") (pintype "power_in"))
      (node (ref "IC5") (pin "10") (pinfunction "GND_10") (pintype "power_in"))
      (node (ref "IC5") (pin "11") (pinfunction "GND_11") (pintype "power_in"))
      (node (ref "IC5") (pin "12") (pinfunction "GND_12") (pintype "power_in"))
      (node (ref "IC5") (pin "16") (pinfunction "GND_16") (pintype "power_in"))
      (node (ref "IC5") (pin "17") (pinfunction "GND_17") (pintype "power_in"))
      (node (ref "IC5") (pin "21") (pinfunction "GND_21") (pintype "power_in"))
      (node (ref "IC5") (pin "22") (pinfunction "GND_22") (pintype "power_in"))
      (node (ref "IC5") (pin "23") (pinfunction "GND_23") (pintype "power_in"))
      (node (ref "IC5") (pin "24") (pinfunction "GND_24") (pintype "power_in"))
      (node (ref "IC5") (pin "25") (pinfunction "GND_25") (pintype "power_in"))
      (node (ref "IC5") (pin "29") (pinfunction "GND_29") (pintype "power_in"))
      (node (ref "IC5") (pin "30") (pinfunction "GND_30") (pintype "power_in"))
      (node (ref "IC5") (pin "8") (pinfunction "GND_8") (pintype "power_in"))
      (node (ref "IC6") (pin "2") (pinfunction "GND_2") (pintype "passive"))
      (node (ref "IC8") (pin "8") (pinfunction "GND_8") (pintype "power_in"))
      (node (ref "IC9") (pin "8") (pinfunction "GND_8") (pintype "power_in"))
      (node (ref "JP6") (pin "4") (pinfunction "4_4") (pintype "passive"))
      (node (ref "POWER") (pin "6") (pinfunction "6_6") (pintype "passive"))
      (node (ref "POWER") (pin "7") (pinfunction "7_7") (pintype "passive"))
      (node (ref "R13") (pin "1") (pinfunction "1_1") (pintype "passive"))
      (node (ref "R14") (pin "1") (pinfunction "1_1") (pintype "passive"))
      (node (ref "R16") (pin "1") (pinfunction "1_1") (pintype "passive"))
      (node (ref "R7") (pin "2") (pinfunction "2_2") (pintype "passive"))
      (node (ref "SW1") (pin "2") (pinfunction "2_2") (pintype "passive"))
      (node (ref "SW1") (pin "2A") (pinfunction "2_2A") (pintype "passive"))
      (node (ref "SW2") (pin "2") (pinfunction "2_2") (pintype "passive"))
      (node (ref "SW2") (pin "2A") (pinfunction "2_2A") (pintype "passive"))
      (node (ref "SW3") (pin "2") (pinfunction "2_2") (pintype "passive"))
      (node (ref "SW3") (pin "2A") (pinfunction "2_2A") (pintype "passive"))
      (node (ref "SW4") (pin "2") (pinfunction "2_2") (pintype "passive"))
      (node (ref "SW4") (pin "2A") (pinfunction "2_2A") (pintype "passive"))
      (node (ref "T1") (pin "2") (pinfunction "S_2") (pintype "passive"))
      (node (ref "T2") (pin "2") (pinfunction "S_2") (pintype "passive"))
      (node (ref "T3") (pin "2") (pinfunction "S_2") (pintype "passive"))
      (node (ref "X1") (pin "0") (pinfunction "0_0") (pintype "passive"))
    )
    (net (code "72") (name "Net-(C9-Pad2)") (class "Default")
      (node (ref "C9") (pin "2") (pinfunction "2_2") (pintype "passive"))
      (node (ref "R14") (pin "2") (pinfunction "2_2") (pintype "passive"))
    )
    (net (code "73") (name "Net-(C10-Pad2)") (class "Default")
      (node (ref "C10") (pin "2") (pinfunction "2_2") (pintype "passive"))
      (node (ref "R15") (pin "2") (pinfunction "2_2") (pintype "passive"))
    )
    (net (code "74") (name "Net-(CON2B-10)") (class "Default")
      (node (ref "CON2") (pin "11") (pinfunction "4_11") (pintype "passive"))
      (node (ref "CON2") (pin "14") (pinfunction "5_14") (pintype "passive"))
      (node (ref "CON2") (pin "17") (pinfunction "6_17") (pintype "passive"))
      (node (ref "CON2") (pin "20") (pinfunction "7_20") (pintype "passive"))
      (node (ref "CON2") (pin "23") (pinfunction "8_23") (pintype "passive"))
      (node (ref "CON2") (pin "26") (pinfunction "9_26") (pintype "passive"))
      (node (ref "CON2") (pin "29") (pinfunction "10_29") (pintype "passive"))
      (node (ref "CON2") (pin "32") (pinfunction "11_32") (pintype "passive"))
      (node (ref "CON2") (pin "35") (pinfunction "12_35") (pintype "passive"))
      (node (ref "CON2") (pin "38") (pinfunction "13_38") (pintype "passive"))
      (node (ref "CON2") (pin "41") (pinfunction "14_41") (pintype "passive"))
      (node (ref "CON2") (pin "44") (pinfunction "15_44") (pintype "passive"))
      (node (ref "CON2") (pin "47") (pinfunction "16_47") (pintype "passive"))
      (node (ref "CON2") (pin "5") (pinfunction "2_5") (pintype "passive"))
      (node (ref "CON2") (pin "50") (pinfunction "17_50") (pintype "passive"))
      (node (ref "CON2") (pin "8") (pinfunction "3_8") (pintype "passive"))
      (node (ref "R27") (pin "2") (pinfunction "2_2") (pintype "passive"))
    )
    (net (code "75") (name "Net-(D2-PadA)") (class "Default")
      (node (ref "D2") (pin "A") (pinfunction "A_A") (pintype "passive"))
      (node (ref "R2") (pin "2") (pinfunction "2_2") (pintype "passive"))
    )
    (net (code "76") (name "Net-(D3-PadA)") (class "Default")
      (node (ref "D3") (pin "A") (pinfunction "A_A") (pintype "passive"))
      (node (ref "R3") (pin "2") (pinfunction "2_2") (pintype "passive"))
    )
    (net (code "77") (name "Net-(D4-PadK)") (class "Default")
      (node (ref "D4") (pin "K") (pinfunction "K_K") (pintype "passive"))
      (node (ref "R8") (pin "1") (pinfunction "1_1") (pintype "passive"))
    )
    (net (code "78") (name "Net-(D5-PadA)") (class "Default")
      (node (ref "D5") (pin "A") (pinfunction "A_A") (pintype "passive"))
      (node (ref "R9") (pin "1") (pinfunction "1_1") (pintype "passive"))
    )
    (net (code "79") (name "Net-(IC1-COMP)") (class "Default")
      (node (ref "C9") (pin "1") (pinfunction "1_1") (pintype "passive"))
      (node (ref "IC1") (pin "5") (pinfunction "COMP_5") (pintype "input"))
    )
    (net (code "80") (name "Net-(IC1-FB)") (class "Default")
      (node (ref "IC1") (pin "4") (pinfunction "FB_4") (pintype "input"))
      (node (ref "R12") (pin "1") (pinfunction "1_1") (pintype "passive"))
      (node (ref "R13") (pin "2") (pinfunction "2_2") (pintype "passive"))
      (node (ref "R15") (pin "1") (pinfunction "1_1") (pintype "passive"))
    )
    (net (code "81") (name "Net-(IC2-CTS)") (class "Default")
      (node (ref "IC2") (pin "15") (pinfunction "RTS_15") (pintype "output"))
      (node (ref "IC2") (pin "16") (pinfunction "CTS_16") (pintype "input"))
    )
    (net (code "82") (name "Net-(IC2-GPIO2(CONN))") (class "Default")
      (node (ref "IC2") (pin "19") (pinfunction "GPIO2(CONN)_19") (pintype "bidirectional"))
      (node (ref "R9") (pin "2") (pinfunction "2_2") (pintype "passive"))
    )
    (net (code "83") (name "Net-(IC2-GPIO8(RX{slash}TX))") (class "Default")
      (node (ref "IC2") (pin "31") (pinfunction "GPIO8(RX/TX)_31") (pintype "bidirectional"))
      (node (ref "R8") (pin "2") (pinfunction "2_2") (pintype "passive"))
    )
    (net (code "84") (name "Net-(IC2-RX)") (class "Default")
      (node (ref "IC2") (pin "13") (pinfunction "RX_13") (pintype "input"))
      (node (ref "R11") (pin "1") (pinfunction "1_1") (pintype "passive"))
    )
    (net (code "85") (name "Net-(IC2-TX)") (class "Default")
      (node (ref "IC2") (pin "14") (pinfunction "TX_14") (pintype "output"))
      (node (ref "R10") (pin "1") (pinfunction "1_1") (pintype "passive"))
    )
    (net (code "86") (name "Net-(IC2-~{RESET})") (class "Default")
      (node (ref "IC2") (pin "5") (pinfunction "~{RESET}_5") (pintype "input"))
      (node (ref "R23") (pin "2") (pinfunction "2_2") (pintype "passive"))
    )
    (net (code "87") (name "Net-(IC5-C1N)") (class "Default")
      (node (ref "C17") (pin "1") (pinfunction "1_1") (pintype "passive"))
      (node (ref "IC5") (pin "5") (pinfunction "C1N_5") (pintype "bidirectional"))
    )
    (net (code "88") (name "Net-(IC5-C1P)") (class "Default")
      (node (ref "C17") (pin "2") (pinfunction "2_2") (pintype "passive"))
      (node (ref "IC5") (pin "4") (pinfunction "C1P_4") (pintype "bidirectional"))
    )
    (net (code "89") (name "Net-(IC5-C2N)") (class "Default")
      (node (ref "C16") (pin "1") (pinfunction "1_1") (pintype "passive"))
      (node (ref "IC5") (pin "3") (pinfunction "C2N_3") (pintype "bidirectional"))
    )
    (net (code "90") (name "Net-(IC5-C2P)") (class "Default")
      (node (ref "C16") (pin "2") (pinfunction "2_2") (pintype "passive"))
      (node (ref "IC5") (pin "2") (pinfunction "C2P_2") (pintype "bidirectional"))
    )
    (net (code "91") (name "Net-(IC5-D{slash}~{C})") (class "Default")
      (node (ref "IC5") (pin "15") (pinfunction "D/~{C}_15") (pintype "input"))
      (node (ref "R19") (pin "1") (pinfunction "1_1") (pintype "passive"))
    )
    (net (code "92") (name "Net-(IC5-IREF)") (class "Default")
      (node (ref "IC5") (pin "26") (pinfunction "IREF_26") (pintype "input"))
      (node (ref "R16") (pin "2") (pinfunction "2_2") (pintype "passive"))
    )
    (net (code "93") (name "Net-(IC5-MOSI)") (class "Default")
      (node (ref "IC5") (pin "19") (pinfunction "MOSI_19") (pintype "input"))
      (node (ref "R18") (pin "1") (pinfunction "1_1") (pintype "passive"))
    )
    (net (code "94") (name "Net-(IC5-SCK)") (class "Default")
      (node (ref "IC5") (pin "18") (pinfunction "SCK_18") (pintype "input"))
      (node (ref "R17") (pin "1") (pinfunction "1_1") (pintype "passive"))
    )
    (net (code "95") (name "Net-(IC5-VCOMH)") (class "Default")
      (node (ref "C18") (pin "2") (pinfunction "2_2") (pintype "passive"))
      (node (ref "IC5") (pin "27") (pinfunction "VCOMH_27") (pintype "output"))
    )
    (net (code "96") (name "Net-(IC5-~{CS})") (class "Default")
      (node (ref "IC5") (pin "13") (pinfunction "~{CS}_13") (pintype "input"))
      (node (ref "R20") (pin "1") (pinfunction "1_1") (pintype "passive"))
    )
    (net (code "97") (name "Net-(IC5-~{RESET})") (class "Default")
      (node (ref "IC5") (pin "14") (pinfunction "~{RESET}_14") (pintype "input"))
      (node (ref "R21") (pin "1") (pinfunction "1_1") (pintype "passive"))
    )
    (net (code "98") (name "Net-(IC8-OUT1)") (class "Default")
      (node (ref "CON4") (pin "2") (pinfunction "2_2") (pintype "passive"))
      (node (ref "IC8") (pin "1") (pinfunction "OUT1_1") (pintype "output"))
    )
    (net (code "99") (name "Net-(IC8-OUT2)") (class "Default")
      (node (ref "CON4") (pin "1") (pinfunction "1_1") (pintype "passive"))
      (node (ref "IC8") (pin "7") (pinfunction "OUT2_7") (pintype "output"))
    )
    (net (code "100") (name "Net-(IC9-OUT1)") (class "Default")
      (node (ref "CON3") (pin "2") (pinfunction "2_2") (pintype "passive"))
      (node (ref "IC9") (pin "1") (pinfunction "OUT1_1") (pintype "output"))
    )
    (net (code "101") (name "Net-(IC9-OUT2)") (class "Default")
      (node (ref "CON3") (pin "1") (pinfunction "1_1") (pintype "passive"))
      (node (ref "IC9") (pin "7") (pinfunction "OUT2_7") (pintype "output"))
    )
    (net (code "102") (name "Net-(T1-D)") (class "Default")
      (node (ref "CON6") (pin "1") (pinfunction "1_1") (pintype "passive"))
      (node (ref "T1") (pin "3") (pinfunction "D_3") (pintype "passive"))
    )
    (net (code "103") (name "Net-(T1-G)") (class "Default")
      (node (ref "R26") (pin "2") (pinfunction "2_2") (pintype "passive"))
      (node (ref "T1") (pin "1") (pinfunction "G_1") (pintype "passive"))
    )
    (net (code "104") (name "Net-(T2-D)") (class "Default")
      (node (ref "T2") (pin "3") (pinfunction "D_3") (pintype "passive"))
      (node (ref "Y2") (pin "-") (pinfunction "-_-") (pintype "passive"))
    )
    (net (code "105") (name "Net-(T3-D)") (class "Default")
      (node (ref "CON5") (pin "1") (pinfunction "1_1") (pintype "passive"))
      (node (ref "T3") (pin "3") (pinfunction "D_3") (pintype "passive"))
    )
    (net (code "106") (name "Net-(T3-G)") (class "Default")
      (node (ref "R25") (pin "2") (pinfunction "2_2") (pintype "passive"))
      (node (ref "T3") (pin "1") (pinfunction "G_1") (pintype "passive"))
    )
    (net (code "107") (name "unconnected-(CON2C-1-Pad3)") (class "Default")
      (node (ref "CON2") (pin "3") (pinfunction "1_3") (pintype "passive"))
    )
    (net (code "108") (name "unconnected-(IC2-GPIO11(RTS)-Pad34)") (class "Default")
      (node (ref "IC2") (pin "34") (pinfunction "GPIO11(RTS)_34") (pintype "bidirectional"))
    )
    (net (code "109") (name "unconnected-(IC4-(A8)PC0-Pad53)") (class "Default")
      (node (ref "IC4") (pin "53") (pinfunction "(A8)PC0_53") (pintype "bidirectional"))
    )
    (net (code "110") (name "unconnected-(IC4-(A9)PC1-Pad54)") (class "Default")
      (node (ref "IC4") (pin "54") (pinfunction "(A9)PC1_54") (pintype "bidirectional"))
    )
    (net (code "111") (name "unconnected-(IC4-(A10)PC2-Pad55)") (class "Default")
      (node (ref "IC4") (pin "55") (pinfunction "(A10)PC2_55") (pintype "bidirectional"))
    )
    (net (code "112") (name "unconnected-(IC4-(A11)PC3-Pad56)") (class "Default")
      (node (ref "IC4") (pin "56") (pinfunction "(A11)PC3_56") (pintype "bidirectional"))
    )
    (net (code "113") (name "unconnected-(IC4-(A12)PC4-Pad57)") (class "Default")
      (node (ref "IC4") (pin "57") (pinfunction "(A12)PC4_57") (pintype "bidirectional"))
    )
    (net (code "114") (name "unconnected-(IC4-(A13)PC5-Pad58)") (class "Default")
      (node (ref "IC4") (pin "58") (pinfunction "(A13)PC5_58") (pintype "bidirectional"))
    )
    (net (code "115") (name "unconnected-(IC4-(A14)PC6-Pad59)") (class "Default")
      (node (ref "IC4") (pin "59") (pinfunction "(A14)PC6_59") (pintype "bidirectional"))
    )
    (net (code "116") (name "unconnected-(IC4-(A15)PC7-Pad60)") (class "Default")
      (node (ref "IC4") (pin "60") (pinfunction "(A15)PC7_60") (pintype "bidirectional"))
    )
    (net (code "117") (name "unconnected-(IC4-(AD2)PA2-Pad76)") (class "Default")
      (node (ref "IC4") (pin "76") (pinfunction "(AD2)PA2_76") (pintype "bidirectional"))
    )
    (net (code "118") (name "unconnected-(IC4-(AD3)PA3-Pad75)") (class "Default")
      (node (ref "IC4") (pin "75") (pinfunction "(AD3)PA3_75") (pintype "bidirectional"))
    )
    (net (code "119") (name "unconnected-(IC4-(AD4)PA4-Pad74)") (class "Default")
      (node (ref "IC4") (pin "74") (pinfunction "(AD4)PA4_74") (pintype "bidirectional"))
    )
    (net (code "120") (name "unconnected-(IC4-(AD5)PA5-Pad73)") (class "Default")
      (node (ref "IC4") (pin "73") (pinfunction "(AD5)PA5_73") (pintype "bidirectional"))
    )
    (net (code "121") (name "unconnected-(IC4-(AD6)PA6-Pad72)") (class "Default")
      (node (ref "IC4") (pin "72") (pinfunction "(AD6)PA6_72") (pintype "bidirectional"))
    )
    (net (code "122") (name "unconnected-(IC4-(ALE)PG2-Pad70)") (class "Default")
      (node (ref "IC4") (pin "70") (pinfunction "(ALE)PG2_70") (pintype "bidirectional"))
    )
    (net (code "123") (name "unconnected-(IC4-(CLKO{slash}ICP3{slash}INT7)PE7-Pad9)") (class "Default")
      (node (ref "IC4") (pin "9") (pinfunction "(CLKO/ICP3/INT7)PE7_9") (pintype "bidirectional"))
    )
    (net (code "124") (name "unconnected-(IC4-(RD)PG1-Pad52)") (class "Default")
      (node (ref "IC4") (pin "52") (pinfunction "(RD)PG1_52") (pintype "bidirectional"))
    )
    (net (code "125") (name "unconnected-(IC4-(T0)PD7-Pad50)") (class "Default")
      (node (ref "IC4") (pin "50") (pinfunction "(T0)PD7_50") (pintype "bidirectional"))
    )
    (net (code "126") (name "unconnected-(IC4-(T1)PD6-Pad49)") (class "Default")
      (node (ref "IC4") (pin "49") (pinfunction "(T1)PD6_49") (pintype "bidirectional"))
    )
    (net (code "127") (name "unconnected-(IC4-(T3{slash}INT6)PE6-Pad8)") (class "Default")
      (node (ref "IC4") (pin "8") (pinfunction "(T3/INT6)PE6_8") (pintype "bidirectional"))
    )
    (net (code "128") (name "unconnected-(IC4-(WR)PG0-Pad51)") (class "Default")
      (node (ref "IC4") (pin "51") (pinfunction "(WR)PG0_51") (pintype "bidirectional"))
    )
    (net (code "129") (name "unconnected-(IC4-(XCK0{slash}AIN0)PE2-Pad4)") (class "Default")
      (node (ref "IC4") (pin "4") (pinfunction "(XCK0/AIN0)PE2_4") (pintype "bidirectional"))
    )
    (net (code "130") (name "unconnected-(IC4-PJ0(RXD3{slash}PCINT9)-Pad63)") (class "Default")
      (node (ref "IC4") (pin "63") (pinfunction "PJ0(RXD3/PCINT9)_63") (pintype "bidirectional"))
    )
    (net (code "131") (name "unconnected-(IC4-PJ1(TXD3{slash}PCINT10)-Pad64)") (class "Default")
      (node (ref "IC4") (pin "64") (pinfunction "PJ1(TXD3/PCINT10)_64") (pintype "bidirectional"))
    )
    (net (code "132") (name "unconnected-(IC4-PJ2(XCK3{slash}PCINT11)-Pad65)") (class "Default")
      (node (ref "IC4") (pin "65") (pinfunction "PJ2(XCK3/PCINT11)_65") (pintype "bidirectional"))
    )
    (net (code "133") (name "unconnected-(IC4-PJ3(PCINT12)-Pad66)") (class "Default")
      (node (ref "IC4") (pin "66") (pinfunction "PJ3(PCINT12)_66") (pintype "bidirectional"))
    )
    (net (code "134") (name "unconnected-(IC4-PJ4(PCINT13)-Pad67)") (class "Default")
      (node (ref "IC4") (pin "67") (pinfunction "PJ4(PCINT13)_67") (pintype "bidirectional"))
    )
    (net (code "135") (name "unconnected-(IC4-PJ5(PCINT14)-Pad68)") (class "Default")
      (node (ref "IC4") (pin "68") (pinfunction "PJ5(PCINT14)_68") (pintype "bidirectional"))
    )
    (net (code "136") (name "unconnected-(IC4-PJ6(PCINT15)-Pad69)") (class "Default")
      (node (ref "IC4") (pin "69") (pinfunction "PJ6(PCINT15)_69") (pintype "bidirectional"))
    )
    (net (code "137") (name "unconnected-(IC4-PJ7-Pad79)") (class "Default")
      (node (ref "IC4") (pin "79") (pinfunction "PJ7_79") (pintype "bidirectional"))
    )
    (net (code "138") (name "unconnected-(IC4-PL0(ICP4)-Pad35)") (class "Default")
      (node (ref "IC4") (pin "35") (pinfunction "PL0(ICP4)_35") (pintype "bidirectional"))
    )
    (net (code "139") (name "unconnected-(IC4-PL1(ICP5)-Pad36)") (class "Default")
      (node (ref "IC4") (pin "36") (pinfunction "PL1(ICP5)_36") (pintype "bidirectional"))
    )
    (net (code "140") (name "unconnected-(POWER-Pad1)") (class "Default")
      (node (ref "POWER") (pin "1") (pinfunction "1_1") (pintype "passive"))
    )
  )
)
